# Power_Supplies.net
KiCad netlist of a schematic drawn in Altium Designer
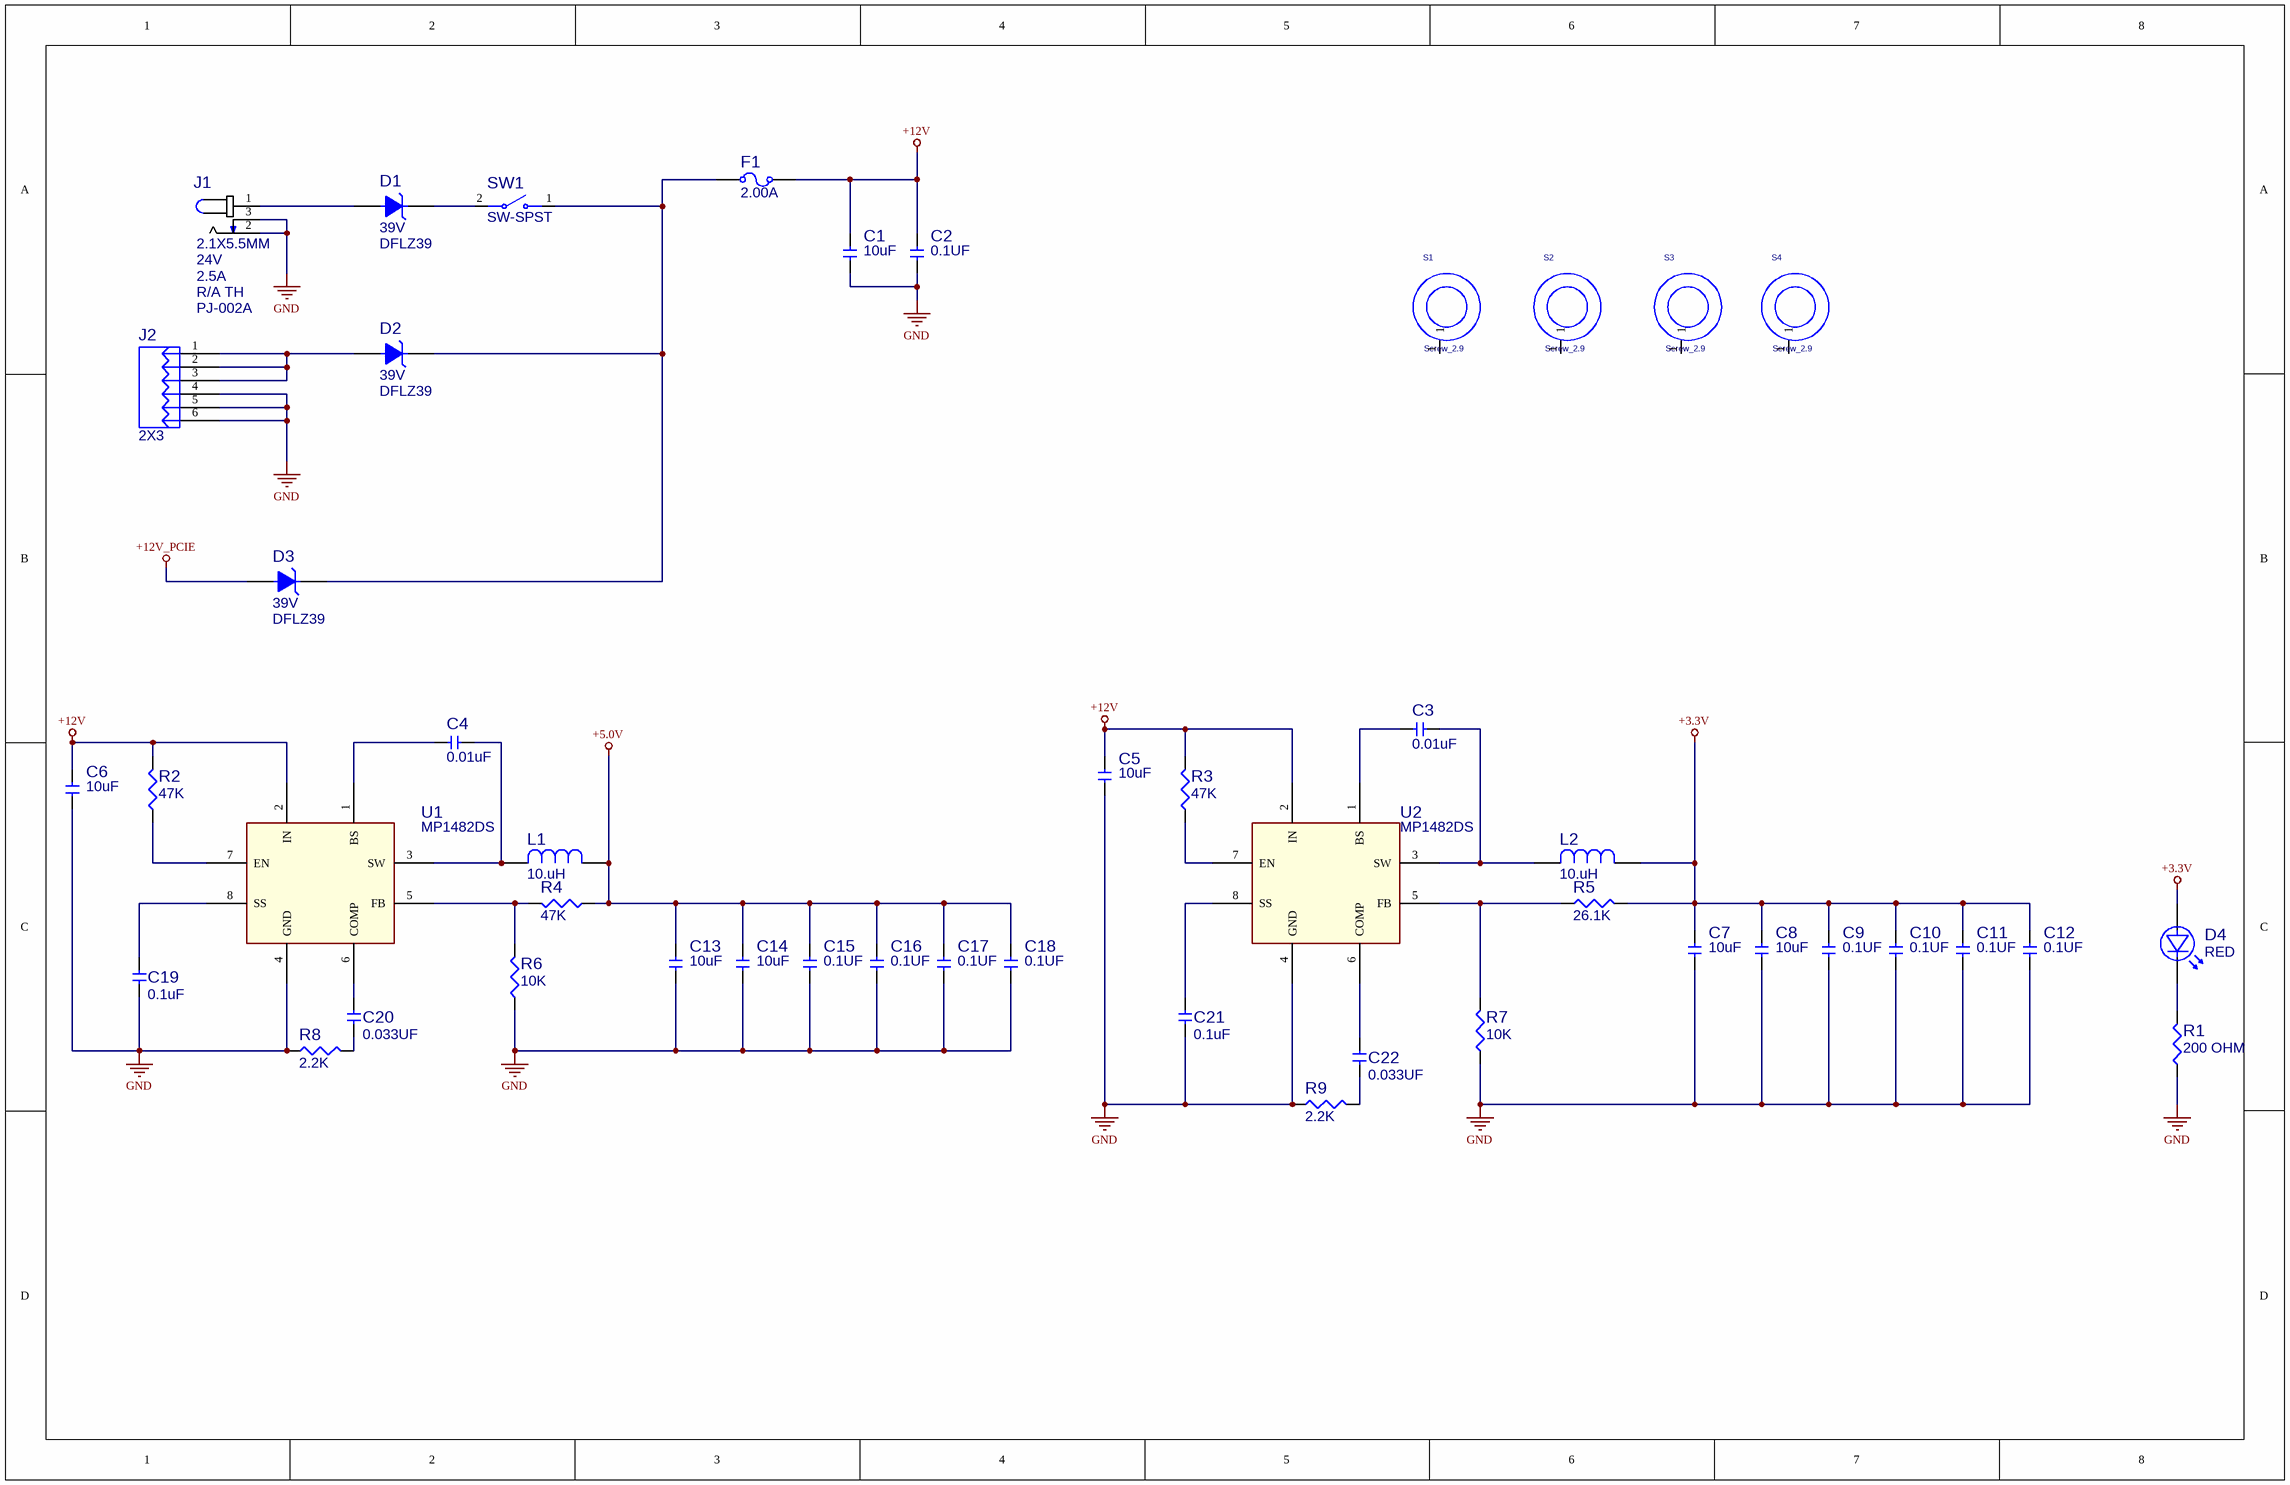
[diagram p0: Power Supplies.SchDoc]

(export (version "E")
  (design (tool "Eeschema 10.0.6"))
  (components
    (comp (ref "C1")
      (value "10uF")
      (footprint "CAPC2012X14N")
      (description "CAP, CER, 10.UF, 25V, 10%, X5R, 0805")
      (fields
        (field (name "MFG PART NUM") "TMK212BBJ106KG-T")
        (field (name "VALENTIUM PART NUM") "<VALENTIUM>")
      )
      (libsource (lib "Capacitors") (part "CAP_0805_10UF_25V"))
    )
    (comp (ref "C2")
      (value "0.1UF")
      (footprint "CAPC1005X06N")
      (description "CAP, CER, 0.1UF, 50V, 10%, X7R, AEC-Q200, 0402")
      (fields
        (field (name "MFG PART NUM") "CGA2B3X7R1H104K050BB")
        (field (name "VALENTIUM PART NUM") "<VALENTIUM>")
      )
      (libsource (lib "Capacitors") (part "CAP_0402_0.1UF_50V"))
    )
    (comp (ref "C3")
      (value "0.01uF")
      (footprint "CAPC1608X10N")
      (description "CAP, CER, 0.01UF, 50V, 10%, X7R, 0603")
      (fields
        (field (name "MFG PART NUM") "C0603C103K5RACTU")
        (field (name "VALENTIUM PART NUM") "<VALENTIUM>")
      )
      (libsource (lib "Capacitors") (part "CAP_0603_0.01UF_50V"))
    )
    (comp (ref "C4")
      (value "0.01uF")
      (footprint "CAPC1608X10N")
      (description "CAP, CER, 0.01UF, 50V, 10%, X7R, 0603")
      (fields
        (field (name "MFG PART NUM") "C0603C103K5RACTU")
        (field (name "VALENTIUM PART NUM") "<VALENTIUM>")
      )
      (libsource (lib "Capacitors") (part "CAP_0603_0.01UF_50V"))
    )
    (comp (ref "C5")
      (value "10uF")
      (footprint "CAPC2012X14N")
      (description "CAP, CER, 10.UF, 25V, 10%, X5R, 0805")
      (fields
        (field (name "MFG PART NUM") "TMK212BBJ106KG-T")
        (field (name "VALENTIUM PART NUM") "<VALENTIUM>")
      )
      (libsource (lib "Capacitors") (part "CAP_0805_10UF_25V"))
    )
    (comp (ref "C6")
      (value "10uF")
      (footprint "CAPC2012X14N")
      (description "CAP, CER, 10.UF, 25V, 10%, X5R, 0805")
      (fields
        (field (name "MFG PART NUM") "TMK212BBJ106KG-T")
        (field (name "VALENTIUM PART NUM") "<VALENTIUM>")
      )
      (libsource (lib "Capacitors") (part "CAP_0805_10UF_25V"))
    )
    (comp (ref "C7")
      (value "10uF")
      (footprint "CAPC2012X14N")
      (description "CAP, CER, 10.UF, 25V, 10%, X5R, 0805")
      (fields
        (field (name "MFG PART NUM") "TMK212BBJ106KG-T")
        (field (name "VALENTIUM PART NUM") "<VALENTIUM>")
      )
      (libsource (lib "Capacitors") (part "CAP_0805_10UF_25V"))
    )
    (comp (ref "C8")
      (value "10uF")
      (footprint "CAPC2012X14N")
      (description "CAP, CER, 10.UF, 25V, 10%, X5R, 0805")
      (fields
        (field (name "MFG PART NUM") "TMK212BBJ106KG-T")
        (field (name "VALENTIUM PART NUM") "<VALENTIUM>")
      )
      (libsource (lib "Capacitors") (part "CAP_0805_10UF_25V"))
    )
    (comp (ref "C9")
      (value "0.1UF")
      (footprint "CAPC1005X06N")
      (description "CAP, CER, 0.1UF, 50V, 10%, X7R, AEC-Q200, 0402")
      (fields
        (field (name "MFG PART NUM") "CGA2B3X7R1H104K050BB")
        (field (name "VALENTIUM PART NUM") "<VALENTIUM>")
      )
      (libsource (lib "Capacitors") (part "CAP_0402_0.1UF_50V"))
    )
    (comp (ref "C10")
      (value "0.1UF")
      (footprint "CAPC1005X06N")
      (description "CAP, CER, 0.1UF, 50V, 10%, X7R, AEC-Q200, 0402")
      (fields
        (field (name "MFG PART NUM") "CGA2B3X7R1H104K050BB")
        (field (name "VALENTIUM PART NUM") "<VALENTIUM>")
      )
      (libsource (lib "Capacitors") (part "CAP_0402_0.1UF_50V"))
    )
    (comp (ref "C11")
      (value "0.1UF")
      (footprint "CAPC1005X06N")
      (description "CAP, CER, 0.1UF, 50V, 10%, X7R, AEC-Q200, 0402")
      (fields
        (field (name "MFG PART NUM") "CGA2B3X7R1H104K050BB")
        (field (name "VALENTIUM PART NUM") "<VALENTIUM>")
      )
      (libsource (lib "Capacitors") (part "CAP_0402_0.1UF_50V"))
    )
    (comp (ref "C12")
      (value "0.1UF")
      (footprint "CAPC1005X06N")
      (description "CAP, CER, 0.1UF, 50V, 10%, X7R, AEC-Q200, 0402")
      (fields
        (field (name "MFG PART NUM") "CGA2B3X7R1H104K050BB")
        (field (name "VALENTIUM PART NUM") "<VALENTIUM>")
      )
      (libsource (lib "Capacitors") (part "CAP_0402_0.1UF_50V"))
    )
    (comp (ref "C13")
      (value "10uF")
      (footprint "CAPC2012X14N")
      (description "CAP, CER, 10.UF, 25V, 10%, X5R, 0805")
      (fields
        (field (name "MFG PART NUM") "TMK212BBJ106KG-T")
        (field (name "VALENTIUM PART NUM") "<VALENTIUM>")
      )
      (libsource (lib "Capacitors") (part "CAP_0805_10UF_25V"))
    )
    (comp (ref "C14")
      (value "10uF")
      (footprint "CAPC2012X14N")
      (description "CAP, CER, 10.UF, 25V, 10%, X5R, 0805")
      (fields
        (field (name "MFG PART NUM") "TMK212BBJ106KG-T")
        (field (name "VALENTIUM PART NUM") "<VALENTIUM>")
      )
      (libsource (lib "Capacitors") (part "CAP_0805_10UF_25V"))
    )
    (comp (ref "C15")
      (value "0.1UF")
      (footprint "CAPC1005X06N")
      (description "CAP, CER, 0.1UF, 50V, 10%, X7R, AEC-Q200, 0402")
      (fields
        (field (name "MFG PART NUM") "CGA2B3X7R1H104K050BB")
        (field (name "VALENTIUM PART NUM") "<VALENTIUM>")
      )
      (libsource (lib "Capacitors") (part "CAP_0402_0.1UF_50V"))
    )
    (comp (ref "C16")
      (value "0.1UF")
      (footprint "CAPC1005X06N")
      (description "CAP, CER, 0.1UF, 50V, 10%, X7R, AEC-Q200, 0402")
      (fields
        (field (name "MFG PART NUM") "CGA2B3X7R1H104K050BB")
        (field (name "VALENTIUM PART NUM") "<VALENTIUM>")
      )
      (libsource (lib "Capacitors") (part "CAP_0402_0.1UF_50V"))
    )
    (comp (ref "C17")
      (value "0.1UF")
      (footprint "CAPC1005X06N")
      (description "CAP, CER, 0.1UF, 50V, 10%, X7R, AEC-Q200, 0402")
      (fields
        (field (name "MFG PART NUM") "CGA2B3X7R1H104K050BB")
        (field (name "VALENTIUM PART NUM") "<VALENTIUM>")
      )
      (libsource (lib "Capacitors") (part "CAP_0402_0.1UF_50V"))
    )
    (comp (ref "C18")
      (value "0.1UF")
      (footprint "CAPC1005X06N")
      (description "CAP, CER, 0.1UF, 50V, 10%, X7R, AEC-Q200, 0402")
      (fields
        (field (name "MFG PART NUM") "CGA2B3X7R1H104K050BB")
        (field (name "VALENTIUM PART NUM") "<VALENTIUM>")
      )
      (libsource (lib "Capacitors") (part "CAP_0402_0.1UF_50V"))
    )
    (comp (ref "C19")
      (value "0.1uF")
      (footprint "CAPC1608X10N")
      (description "CAP, CER, 0.1UF, 50V, 10%, X7R, 0603")
      (fields
        (field (name "MFG PART NUM") "C0603C104K5RACTU")
        (field (name "VALENTIUM PART NUM") "<VALENTIUM>")
      )
      (libsource (lib "Capacitors") (part "CAP_0603_0.1UF_50V"))
    )
    (comp (ref "C20")
      (value "0.033UF")
      (footprint "CAPC1005X06N")
      (description "CAP, CER, 0.033UF, 50V, 10%, X7R, AEC-Q200, 0402")
      (fields
        (field (name "MFG PART NUM") "CGA2B3X5R1H333K050BB")
        (field (name "VALENTIUM PART NUM") "<VALENTIUM>")
      )
      (libsource (lib "Capacitors") (part "CAP_0402_0.033UF_50V"))
    )
    (comp (ref "C21")
      (value "0.1uF")
      (footprint "CAPC1608X10N")
      (description "CAP, CER, 0.1UF, 50V, 10%, X7R, 0603")
      (fields
        (field (name "MFG PART NUM") "C0603C104K5RACTU")
        (field (name "VALENTIUM PART NUM") "<VALENTIUM>")
      )
      (libsource (lib "Capacitors") (part "CAP_0603_0.1UF_50V"))
    )
    (comp (ref "C22")
      (value "0.033UF")
      (footprint "CAPC1005X06N")
      (description "CAP, CER, 0.033UF, 50V, 10%, X7R, AEC-Q200, 0402")
      (fields
        (field (name "MFG PART NUM") "CGA2B3X5R1H333K050BB")
        (field (name "VALENTIUM PART NUM") "<VALENTIUM>")
      )
      (libsource (lib "Capacitors") (part "CAP_0402_0.033UF_50V"))
    )
    (comp (ref "D1")
      (value "DFLZ39")
      (footprint "SODFL370X135-2N")
      (description "DIO, ZENER, DFLZ39, 39V, 5%, 1W, SOD123FL")
      (fields
        (field (name "MFG PART NUM") "DFLZ39-TP")
        (field (name "P1") "39V")
        (field (name "VALENTIUM PART NUM") "<VALENTIUM>")
      )
      (libsource (lib "Passives") (part "DFLZ39"))
    )
    (comp (ref "D2")
      (value "DFLZ39")
      (footprint "SODFL370X135-2N")
      (description "DIO, ZENER, DFLZ39, 39V, 5%, 1W, SOD123FL")
      (fields
        (field (name "MFG PART NUM") "DFLZ39-TP")
        (field (name "P1") "39V")
        (field (name "VALENTIUM PART NUM") "<VALENTIUM>")
      )
      (libsource (lib "Passives") (part "DFLZ39"))
    )
    (comp (ref "D3")
      (value "DFLZ39")
      (footprint "SODFL370X135-2N")
      (description "DIO, ZENER, DFLZ39, 39V, 5%, 1W, SOD123FL")
      (fields
        (field (name "MFG PART NUM") "DFLZ39-TP")
        (field (name "P1") "39V")
        (field (name "VALENTIUM PART NUM") "<VALENTIUM>")
      )
      (libsource (lib "Passives") (part "DFLZ39"))
    )
    (comp (ref "D4")
      (value "RED")
      (footprint "DIOM1608X06N")
      (description "LED, RED, SML-LX0603, 635NM, 2V, 20MA, 0603")
      (fields
        (field (name "MFG PART NUM") "SML-LX0603IW-TR")
        (field (name "VALENTIUM PART NUM") "<VALENTIUM>")
      )
      (libsource (lib "Passives") (part "SMTLED_RED_0603_SML"))
    )
    (comp (ref "F1")
      (value "2.00A")
      (footprint "FUSM1608X60N")
      (description "FUSE SLOW 2.00A 32V M 0603")
      (fields (field (name "MFG PART NUM") "SF-0603S200-2") (field (name "VALENTIUM PART NUM") "<VALENTIUM>"))
      (libsource (lib "Passives") (part "FUSE_0603_2.00A"))
    )
    (comp (ref "J1")
      (value "PJ-002A")
      (footprint "CUI_PJ-002A")
      (description "CONN, JACK, PJ-002A, 2.1X5.5MM, 24V 2.5A, R/A TH, SPST-NC")
      (fields
        (field (name "VALENTIUM PART NUM") "<VALENTIUM>")
        (field (name "P1") "2.1X5.5MM")
        (field (name "P2") "24V")
        (field (name "P3") "2.5A")
        (field (name "SIZE") "R/A TH")
      )
      (libsource (lib "Connectors") (part "PJ-002A"))
    )
    (comp (ref "J2")
      (value "2X3")
      (footprint "39-30-1060")
      (description "CONN, HDR, 2X3, R/A, 4.2MM, TH, MINI-FIT JR")
      (fields (field (name "MFG PART NUM") "105314-1206") (field (name "VALENTIUM PART NUM") "<VALENTIUM>"))
      (libsource (lib "Connectors") (part "39-30-1060"))
    )
    (comp (ref "L1")
      (value "10.uH")
      (footprint "IND_PM124SH")
      (description "IND, PWR, 10.uH, 20%, 4A, 0.04DCR, 12.5X12.5MM, SHLD")
      (fields
        (field (name "MFG PART NUM") "PM124SH-100M-RC")
        (field (name "VALENTIUM PART NUM") "<VALENTIUM>")
      )
      (libsource (lib "Passives") (part "PM124SH-100M-RC"))
    )
    (comp (ref "L2")
      (value "10.uH")
      (footprint "IND_PM124SH")
      (description "IND, PWR, 10.uH, 20%, 4A, 0.04DCR, 12.5X12.5MM, SHLD")
      (fields
        (field (name "MFG PART NUM") "PM124SH-100M-RC")
        (field (name "VALENTIUM PART NUM") "<VALENTIUM>")
      )
      (libsource (lib "Passives") (part "PM124SH-100M-RC"))
    )
    (comp (ref "R1")
      (value "200 OHM")
      (footprint "RESC1608X50N")
      (description "RES, 200 OHM, 1%, 1/10W, TF, 0603")
      (fields (field (name "MFG PART NUM") "ERJ-3EKF2000V") (field (name "VELENTIUM PART NUM") "<VELENTIUM>"))
      (libsource (lib "Resistors") (part "RES_0603_200"))
    )
    (comp (ref "R2")
      (value "47K")
      (footprint "RESC1608X50N")
      (description "RES, 47K, 1%, 1/10W, TF, 0603")
      (fields (field (name "MFG PART NUM") "ERJ-3EKF4702V") (field (name "VELENTIUM PART NUM") "<VELENTIUM>"))
      (libsource (lib "Resistors") (part "RES_0603_47K"))
    )
    (comp (ref "R3")
      (value "47K")
      (footprint "RESC1608X50N")
      (description "RES, 47K, 1%, 1/10W, TF, 0603")
      (fields (field (name "MFG PART NUM") "ERJ-3EKF4702V") (field (name "VELENTIUM PART NUM") "<VELENTIUM>"))
      (libsource (lib "Resistors") (part "RES_0603_47K"))
    )
    (comp (ref "R4")
      (value "47K")
      (footprint "RESC1608X50N")
      (description "RES, 47K, 1%, 1/10W, TF, 0603")
      (fields (field (name "MFG PART NUM") "ERJ-3EKF4702V") (field (name "VELENTIUM PART NUM") "<VELENTIUM>"))
      (libsource (lib "Resistors") (part "RES_0603_47K"))
    )
    (comp (ref "R5")
      (value "26.1K")
      (footprint "RESC1608X50N")
      (description "RES, 26.1K, 1%, 1/10W, TF, 0603")
      (fields (field (name "MFG PART NUM") "ERJ-3EKF2612V") (field (name "VELENTIUM PART NUM") "<VELENTIUM>"))
      (libsource (lib "Resistors") (part "RES_0603_26.1K"))
    )
    (comp (ref "R6")
      (value "10K")
      (footprint "RESC1608X50N")
      (description "RES, 10K, 1%, 1/10W, TF, 0603")
      (fields (field (name "MFG PART NUM") "ERJ-3EKF1002V") (field (name "VELENTIUM PART NUM") "<VELENTIUM>"))
      (libsource (lib "Resistors") (part "RES_0603_10K"))
    )
    (comp (ref "R7")
      (value "10K")
      (footprint "RESC1608X50N")
      (description "RES, 10K, 1%, 1/10W, TF, 0603")
      (fields (field (name "MFG PART NUM") "ERJ-3EKF1002V") (field (name "VELENTIUM PART NUM") "<VELENTIUM>"))
      (libsource (lib "Resistors") (part "RES_0603_10K"))
    )
    (comp (ref "R8")
      (value "2.2K")
      (footprint "RESC1608X50N")
      (description "RES, 2.2K, 1%, 1/10W, TF, 0603")
      (fields (field (name "MFG PART NUM") "ERJ-3EKF2201V") (field (name "VELENTIUM PART NUM") "<VELENTIUM>"))
      (libsource (lib "Resistors") (part "RES_0603_2.2K"))
    )
    (comp (ref "R9")
      (value "2.2K")
      (footprint "RESC1608X50N")
      (description "RES, 2.2K, 1%, 1/10W, TF, 0603")
      (fields (field (name "MFG PART NUM") "ERJ-3EKF2201V") (field (name "VELENTIUM PART NUM") "<VELENTIUM>"))
      (libsource (lib "Resistors") (part "RES_0603_2.2K"))
    )
    (comp (ref "S1")
      (value "Screw_2.9")
      (footprint "MH_250H125")
      (description "FH140 Screw,Diameter 2.9mm")
      (fields (field (name "PART NUMBER") "454") (field (name "MANUFACTURER") "NA"))
      (libsource (lib "AX7103_AD_Schematics") (part "screw_0"))
    )
    (comp (ref "S2")
      (value "Screw_2.9")
      (footprint "MH_250H125")
      (description "FH140 Screw,Diameter 2.9mm")
      (fields (field (name "PART NUMBER") "454") (field (name "MANUFACTURER") "NA"))
      (libsource (lib "AX7103_AD_Schematics") (part "screw_0"))
    )
    (comp (ref "S3")
      (value "Screw_2.9")
      (footprint "MH_250H125")
      (description "FH140 Screw,Diameter 2.9mm")
      (fields (field (name "PART NUMBER") "454") (field (name "MANUFACTURER") "NA"))
      (libsource (lib "AX7103_AD_Schematics") (part "screw_0"))
    )
    (comp (ref "S4")
      (value "Screw_2.9")
      (footprint "MH_250H125")
      (description "FH140 Screw,Diameter 2.9mm")
      (fields (field (name "PART NUMBER") "454") (field (name "MANUFACTURER") "NA"))
      (libsource (lib "AX7103_AD_Schematics") (part "screw_0"))
    )
    (comp (ref "SW1")
      (value "SW-SPST")
      (footprint "L101011MS02Q")
      (description "SW, SPST, 250V, 2A, SLIDE, ON-OFF, TH")
      (fields (field (name "MFG PART NUM") "L101011MS02Q") (field (name "VALENTIUM PART NUM") "<VALENTIUM>"))
      (libsource (lib "Miscellaneous") (part "L101011MS02Q"))
    )
    (comp (ref "U1")
      (value "MP1482DS")
      (footprint "SOIC127P600X175-8N")
      (description "IC, DC/DC, MP1482DS, >4.75VIN, 0.923-15V OUT, SOIC8")
      (fields (field (name "MFG PART NUM") "MP1482DS-LF") (field (name "VELENTIUM PART NUM") "<V PART NUM>"))
      (libsource (lib "IntegratedCircuits") (part "MP1482DS"))
    )
    (comp (ref "U2")
      (value "MP1482DS")
      (footprint "SOIC127P600X175-8N")
      (description "IC, DC/DC, MP1482DS, >4.75VIN, 0.923-15V OUT, SOIC8")
      (fields (field (name "MFG PART NUM") "MP1482DS-LF") (field (name "VELENTIUM PART NUM") "<V PART NUM>"))
      (libsource (lib "IntegratedCircuits") (part "MP1482DS"))
    )
  )
  (nets
    (net (code "1") (name "+3.3V") (class "Default")
      (node (ref "C10") (pin "1") (pinfunction "1_1") (pintype "passive"))
      (node (ref "C11") (pin "1") (pinfunction "1_1") (pintype "passive"))
      (node (ref "C12") (pin "1") (pinfunction "1_1") (pintype "passive"))
      (node (ref "C7") (pin "1") (pinfunction "1_1") (pintype "passive"))
      (node (ref "C8") (pin "1") (pinfunction "1_1") (pintype "passive"))
      (node (ref "C9") (pin "1") (pinfunction "1_1") (pintype "passive"))
      (node (ref "D4") (pin "2") (pinfunction "A_2") (pintype "passive"))
      (node (ref "L2") (pin "1") (pintype "passive"))
      (node (ref "R5") (pin "2") (pinfunction "2_2") (pintype "passive"))
    )
    (net (code "2") (name "+5.0V") (class "Default")
      (node (ref "C13") (pin "1") (pinfunction "1_1") (pintype "passive"))
      (node (ref "C14") (pin "1") (pinfunction "1_1") (pintype "passive"))
      (node (ref "C15") (pin "1") (pinfunction "1_1") (pintype "passive"))
      (node (ref "C16") (pin "1") (pinfunction "1_1") (pintype "passive"))
      (node (ref "C17") (pin "1") (pinfunction "1_1") (pintype "passive"))
      (node (ref "C18") (pin "1") (pinfunction "1_1") (pintype "passive"))
      (node (ref "L1") (pin "1") (pintype "passive"))
      (node (ref "R4") (pin "1") (pinfunction "1_1") (pintype "passive"))
    )
    (net (code "3") (name "+12V") (class "Default")
      (node (ref "C1") (pin "1") (pinfunction "1_1") (pintype "passive"))
      (node (ref "C2") (pin "1") (pinfunction "1_1") (pintype "passive"))
      (node (ref "C5") (pin "1") (pinfunction "1_1") (pintype "passive"))
      (node (ref "C6") (pin "1") (pinfunction "1_1") (pintype "passive"))
      (node (ref "F1") (pin "2") (pinfunction "2_2") (pintype "passive"))
      (node (ref "R2") (pin "2") (pinfunction "2_2") (pintype "passive"))
      (node (ref "R3") (pin "2") (pinfunction "2_2") (pintype "passive"))
      (node (ref "U1") (pin "2") (pinfunction "IN_2") (pintype "passive"))
      (node (ref "U2") (pin "2") (pinfunction "IN_2") (pintype "passive"))
    )
    (net (code "4") (name "+12V_PCIE") (class "Default")
      (node (ref "D3") (pin "2") (pinfunction "A_2") (pintype "passive"))
    )
    (net (code "5") (name "GND") (class "Default")
      (node (ref "C1") (pin "2") (pinfunction "2_2") (pintype "passive"))
      (node (ref "C10") (pin "2") (pinfunction "2_2") (pintype "passive"))
      (node (ref "C11") (pin "2") (pinfunction "2_2") (pintype "passive"))
      (node (ref "C12") (pin "2") (pinfunction "2_2") (pintype "passive"))
      (node (ref "C13") (pin "2") (pinfunction "2_2") (pintype "passive"))
      (node (ref "C14") (pin "2") (pinfunction "2_2") (pintype "passive"))
      (node (ref "C15") (pin "2") (pinfunction "2_2") (pintype "passive"))
      (node (ref "C16") (pin "2") (pinfunction "2_2") (pintype "passive"))
      (node (ref "C17") (pin "2") (pinfunction "2_2") (pintype "passive"))
      (node (ref "C18") (pin "2") (pinfunction "2_2") (pintype "passive"))
      (node (ref "C19") (pin "1") (pinfunction "1_1") (pintype "passive"))
      (node (ref "C2") (pin "2") (pinfunction "2_2") (pintype "passive"))
      (node (ref "C21") (pin "1") (pinfunction "1_1") (pintype "passive"))
      (node (ref "C5") (pin "2") (pinfunction "2_2") (pintype "passive"))
      (node (ref "C6") (pin "2") (pinfunction "2_2") (pintype "passive"))
      (node (ref "C7") (pin "2") (pinfunction "2_2") (pintype "passive"))
      (node (ref "C8") (pin "2") (pinfunction "2_2") (pintype "passive"))
      (node (ref "C9") (pin "2") (pinfunction "2_2") (pintype "passive"))
      (node (ref "J1") (pin "2") (pinfunction "2_2") (pintype "passive"))
      (node (ref "J1") (pin "3") (pinfunction "3_3") (pintype "passive"))
      (node (ref "J2") (pin "4") (pintype "passive"))
      (node (ref "J2") (pin "5") (pintype "passive"))
      (node (ref "J2") (pin "6") (pintype "passive"))
      (node (ref "R1") (pin "1") (pinfunction "1_1") (pintype "passive"))
      (node (ref "R6") (pin "1") (pinfunction "1_1") (pintype "passive"))
      (node (ref "R7") (pin "1") (pinfunction "1_1") (pintype "passive"))
      (node (ref "R8") (pin "1") (pinfunction "1_1") (pintype "passive"))
      (node (ref "R9") (pin "1") (pinfunction "1_1") (pintype "passive"))
      (node (ref "U1") (pin "4") (pinfunction "GND_4") (pintype "passive"))
      (node (ref "U2") (pin "4") (pinfunction "GND_4") (pintype "passive"))
    )
    (net (code "6") (name "Net-(C20-Pad2)") (class "Default")
      (node (ref "C20") (pin "2") (pinfunction "2_2") (pintype "passive"))
      (node (ref "R8") (pin "2") (pinfunction "2_2") (pintype "passive"))
    )
    (net (code "7") (name "Net-(C22-Pad2)") (class "Default")
      (node (ref "C22") (pin "2") (pinfunction "2_2") (pintype "passive"))
      (node (ref "R9") (pin "2") (pinfunction "2_2") (pintype "passive"))
    )
    (net (code "8") (name "Net-(D1-A)") (class "Default")
      (node (ref "D1") (pin "2") (pinfunction "A_2") (pintype "passive"))
      (node (ref "J1") (pin "1") (pinfunction "1_1") (pintype "passive"))
    )
    (net (code "9") (name "Net-(D1-C)") (class "Default")
      (node (ref "D1") (pin "1") (pinfunction "C_1") (pintype "passive"))
      (node (ref "SW1") (pin "2") (pintype "passive"))
    )
    (net (code "10") (name "Net-(D2-A)") (class "Default")
      (node (ref "D2") (pin "2") (pinfunction "A_2") (pintype "passive"))
      (node (ref "J2") (pin "1") (pintype "passive"))
      (node (ref "J2") (pin "2") (pintype "passive"))
      (node (ref "J2") (pin "3") (pintype "passive"))
    )
    (net (code "11") (name "Net-(D2-C)") (class "Default")
      (node (ref "D2") (pin "1") (pinfunction "C_1") (pintype "passive"))
      (node (ref "D3") (pin "1") (pinfunction "C_1") (pintype "passive"))
      (node (ref "F1") (pin "1") (pinfunction "1_1") (pintype "passive"))
      (node (ref "SW1") (pin "1") (pintype "passive"))
    )
    (net (code "12") (name "Net-(D4-K)") (class "Default")
      (node (ref "D4") (pin "1") (pinfunction "K_1") (pintype "passive"))
      (node (ref "R1") (pin "2") (pinfunction "2_2") (pintype "passive"))
    )
    (net (code "13") (name "Net-(U1-BS)") (class "Default")
      (node (ref "C4") (pin "1") (pinfunction "1_1") (pintype "passive"))
      (node (ref "U1") (pin "1") (pinfunction "BS_1") (pintype "passive"))
    )
    (net (code "14") (name "Net-(U1-COMP)") (class "Default")
      (node (ref "C20") (pin "1") (pinfunction "1_1") (pintype "passive"))
      (node (ref "U1") (pin "6") (pinfunction "COMP_6") (pintype "passive"))
    )
    (net (code "15") (name "Net-(U1-EN)") (class "Default")
      (node (ref "R2") (pin "1") (pinfunction "1_1") (pintype "passive"))
      (node (ref "U1") (pin "7") (pinfunction "EN_7") (pintype "passive"))
    )
    (net (code "16") (name "Net-(U1-FB)") (class "Default")
      (node (ref "R4") (pin "2") (pinfunction "2_2") (pintype "passive"))
      (node (ref "R6") (pin "2") (pinfunction "2_2") (pintype "passive"))
      (node (ref "U1") (pin "5") (pinfunction "FB_5") (pintype "passive"))
    )
    (net (code "17") (name "Net-(U1-SS)") (class "Default")
      (node (ref "C19") (pin "2") (pinfunction "2_2") (pintype "passive"))
      (node (ref "U1") (pin "8") (pinfunction "SS_8") (pintype "passive"))
    )
    (net (code "18") (name "Net-(U1-SW)") (class "Default")
      (node (ref "C4") (pin "2") (pinfunction "2_2") (pintype "passive"))
      (node (ref "L1") (pin "2") (pintype "passive"))
      (node (ref "U1") (pin "3") (pinfunction "SW_3") (pintype "passive"))
    )
    (net (code "19") (name "Net-(U2-BS)") (class "Default")
      (node (ref "C3") (pin "1") (pinfunction "1_1") (pintype "passive"))
      (node (ref "U2") (pin "1") (pinfunction "BS_1") (pintype "passive"))
    )
    (net (code "20") (name "Net-(U2-COMP)") (class "Default")
      (node (ref "C22") (pin "1") (pinfunction "1_1") (pintype "passive"))
      (node (ref "U2") (pin "6") (pinfunction "COMP_6") (pintype "passive"))
    )
    (net (code "21") (name "Net-(U2-EN)") (class "Default")
      (node (ref "R3") (pin "1") (pinfunction "1_1") (pintype "passive"))
      (node (ref "U2") (pin "7") (pinfunction "EN_7") (pintype "passive"))
    )
    (net (code "22") (name "Net-(U2-FB)") (class "Default")
      (node (ref "R5") (pin "1") (pinfunction "1_1") (pintype "passive"))
      (node (ref "R7") (pin "2") (pinfunction "2_2") (pintype "passive"))
      (node (ref "U2") (pin "5") (pinfunction "FB_5") (pintype "passive"))
    )
    (net (code "23") (name "Net-(U2-SS)") (class "Default")
      (node (ref "C21") (pin "2") (pinfunction "2_2") (pintype "passive"))
      (node (ref "U2") (pin "8") (pinfunction "SS_8") (pintype "passive"))
    )
    (net (code "24") (name "Net-(U2-SW)") (class "Default")
      (node (ref "C3") (pin "2") (pinfunction "2_2") (pintype "passive"))
      (node (ref "L2") (pin "2") (pintype "passive"))
      (node (ref "U2") (pin "3") (pinfunction "SW_3") (pintype "passive"))
    )
    (net (code "25") (name "unconnected-(S1-Pad1)") (class "Default")
      (node (ref "S1") (pin "1") (pinfunction "1_1") (pintype "passive"))
    )
    (net (code "26") (name "unconnected-(S2-Pad1)") (class "Default")
      (node (ref "S2") (pin "1") (pinfunction "1_1") (pintype "passive"))
    )
    (net (code "27") (name "unconnected-(S3-Pad1)") (class "Default")
      (node (ref "S3") (pin "1") (pinfunction "1_1") (pintype "passive"))
    )
    (net (code "28") (name "unconnected-(S4-Pad1)") (class "Default")
      (node (ref "S4") (pin "1") (pinfunction "1_1") (pintype "passive"))
    )
  )
)
